# in_out.net
KiCad netlist of a schematic drawn in Altium Designer
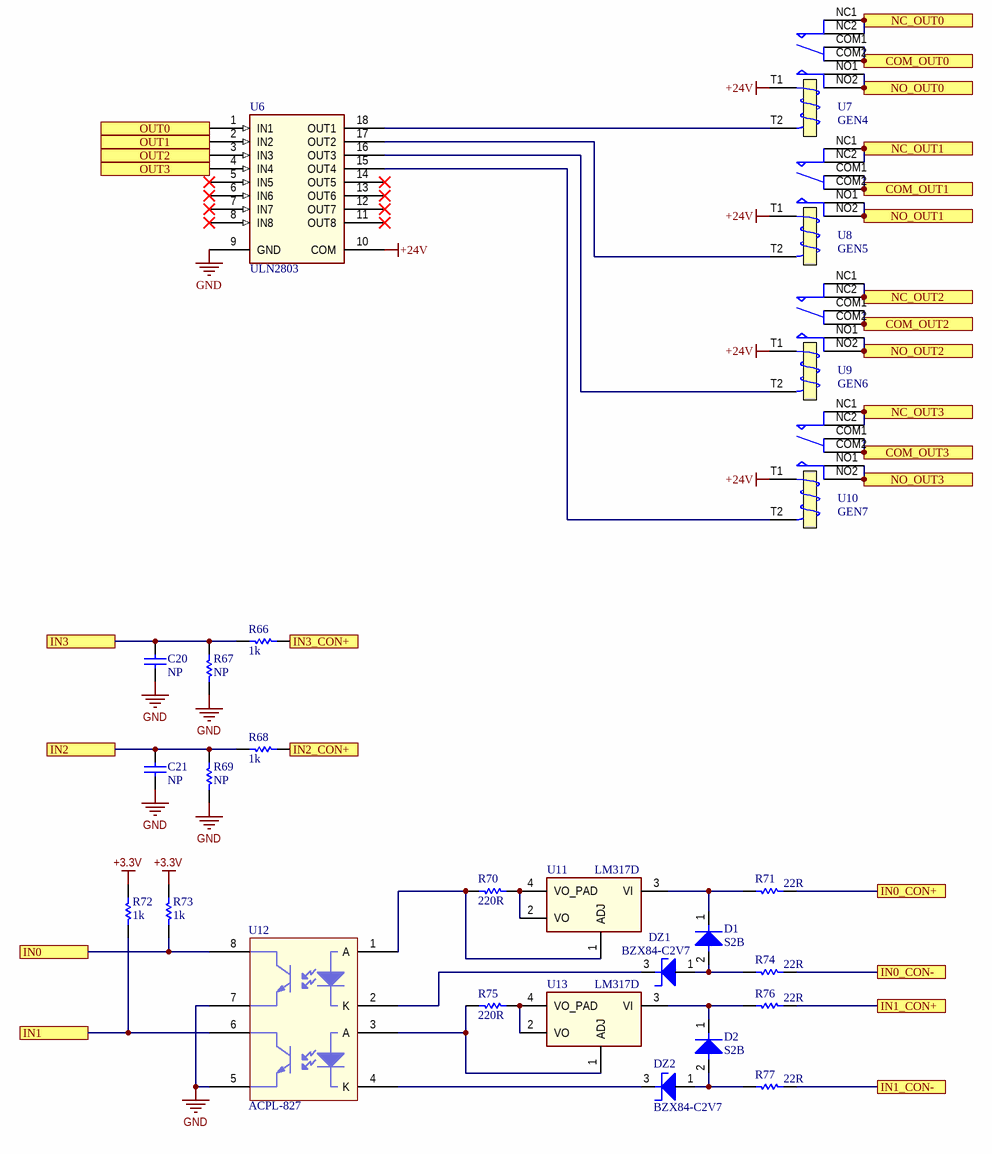
[diagram p0: in_out.SchDoc]

(export (version "E")
  (design (tool "Eeschema 10.0.6"))
  (components
    (comp (ref "C20")
      (value "NP")
      (footprint "0603_[1608]")
      (description "Ceramic X7R 50V")
      (fields (field (name "PUBLISHER") "Altium Limited"))
      (libsource (lib "DEVELER_Library") (part "Cap"))
    )
    (comp (ref "C21")
      (value "NP")
      (footprint "0603_[1608]")
      (description "Ceramic X7R 50V")
      (fields (field (name "PUBLISHER") "Altium Limited"))
      (libsource (lib "DEVELER_Library") (part "Cap"))
    )
    (comp (ref "D1")
      (value "S2B")
      (footprint "DO214AA_K1-A2_SMB")
      (description "S2B Diode")
      (libsource (lib "DEVELER_Library") (part "Diode"))
    )
    (comp (ref "D2")
      (value "S2B")
      (footprint "DO214AA_K1-A2_SMB")
      (description "S2B Diode")
      (libsource (lib "DEVELER_Library") (part "Diode"))
    )
    (comp (ref "DZ1")
      (value "BZX84-C2V7")
      (footprint "SOT-23")
      (description "Zener 2,7V")
      (libsource (lib "DEVELER_Library") (part "ZENER_BZX"))
    )
    (comp (ref "DZ2")
      (value "BZX84-C2V7")
      (footprint "SOT-23")
      (description "Zener 2,7V")
      (libsource (lib "DEVELER_Library") (part "ZENER_BZX"))
    )
    (comp (ref "R66")
      (value "1k")
      (footprint "0603_[1608]")
      (description "Resistor")
      (libsource (lib "DEVELER_Library") (part "Res1"))
    )
    (comp (ref "R67")
      (value "NP")
      (footprint "0603_[1608]")
      (description "Resistor")
      (libsource (lib "DEVELER_Library") (part "Res1"))
    )
    (comp (ref "R68")
      (value "1k")
      (footprint "0603_[1608]")
      (description "Resistor")
      (libsource (lib "DEVELER_Library") (part "Res1"))
    )
    (comp (ref "R69")
      (value "NP")
      (footprint "0603_[1608]")
      (description "Resistor")
      (libsource (lib "DEVELER_Library") (part "Res1"))
    )
    (comp (ref "R70")
      (value "220R")
      (footprint "0603_[1608]")
      (description "Resistor")
      (libsource (lib "DEVELER_Library") (part "Res1"))
    )
    (comp (ref "R71")
      (value "22R")
      (footprint "0603_[1608]")
      (description "Resistor")
      (libsource (lib "DEVELER_Library") (part "Res1"))
    )
    (comp (ref "R72")
      (value "1k")
      (footprint "0603_[1608]")
      (description "Resistor")
      (libsource (lib "DEVELER_Library") (part "Res1"))
    )
    (comp (ref "R73")
      (value "1k")
      (footprint "0603_[1608]")
      (description "Resistor")
      (libsource (lib "DEVELER_Library") (part "Res1"))
    )
    (comp (ref "R74")
      (value "22R")
      (footprint "0603_[1608]")
      (description "Resistor")
      (libsource (lib "DEVELER_Library") (part "Res1"))
    )
    (comp (ref "R75")
      (value "220R")
      (footprint "0603_[1608]")
      (description "Resistor")
      (libsource (lib "DEVELER_Library") (part "Res1"))
    )
    (comp (ref "R76")
      (value "22R")
      (footprint "0603_[1608]")
      (description "Resistor")
      (libsource (lib "DEVELER_Library") (part "Res1"))
    )
    (comp (ref "R77")
      (value "22R")
      (footprint "0603_[1608]")
      (description "Resistor")
      (libsource (lib "DEVELER_Library") (part "Res1"))
    )
    (comp (ref "U6")
      (value "ULN2803")
      (footprint "SOIC18")
      (description "BJT Darlinton Array")
      (libsource (lib "DEVELER_Library") (part "ULN2803"))
    )
    (comp (ref "U7")
      (value "GEN4")
      (footprint "relays_spco_thd_28x12mm_5mm")
      (description "Rele NT75CS16DC12V0.415.0 16A 12V")
      (libsource (lib "develer_library") (part "Relay SPCO_8pin"))
    )
    (comp (ref "U8")
      (value "GEN5")
      (footprint "relays_spco_thd_28x12mm_5mm")
      (description "Rele NT75CS16DC12V0.415.0 16A 12V")
      (libsource (lib "develer_library") (part "Relay SPCO_8pin"))
    )
    (comp (ref "U9")
      (value "GEN6")
      (footprint "relays_spco_thd_28x12mm_5mm")
      (description "Rele NT75CS16DC12V0.415.0 16A 12V")
      (libsource (lib "develer_library") (part "Relay SPCO_8pin"))
    )
    (comp (ref "U10")
      (value "GEN7")
      (footprint "relays_spco_thd_28x12mm_5mm")
      (description "Rele NT75CS16DC12V0.415.0 16A 12V")
      (libsource (lib "develer_library") (part "Relay SPCO_8pin"))
    )
    (comp (ref "U11")
      (value "LM317D")
      (footprint "SOT-223")
      (description "3-Terminal Adjustable Regulator, 3-pin SOT-223")
      (libsource (lib "DEVELER_Library") (part "LM317AT"))
    )
    (comp (ref "U12")
      (value "ACPL-827")
      (footprint "SOIC8_OPTO")
      (description "Optocoupler")
      (libsource (lib "DEVELER_Library") (part "optocoupler 2ch"))
    )
    (comp (ref "U13")
      (value "LM317D")
      (footprint "SOT-223")
      (description "3-Terminal Adjustable Regulator, 3-pin SOT-223")
      (libsource (lib "DEVELER_Library") (part "LM317AT"))
    )
  )
  (nets
    (net (code "1") (name "+3.3V") (class "Default")
      (node (ref "R72") (pin "2") (pinfunction "2_2") (pintype "passive"))
      (node (ref "R73") (pin "2") (pinfunction "2_2") (pintype "passive"))
    )
    (net (code "2") (name "+24V") (class "Default")
      (node (ref "U10") (pin "T1") (pinfunction "T1_T1") (pintype "passive"))
      (node (ref "U6") (pin "10") (pinfunction "COM_10") (pintype "passive"))
      (node (ref "U7") (pin "T1") (pinfunction "T1_T1") (pintype "passive"))
      (node (ref "U8") (pin "T1") (pinfunction "T1_T1") (pintype "passive"))
      (node (ref "U9") (pin "T1") (pinfunction "T1_T1") (pintype "passive"))
    )
    (net (code "3") (name "/COM_OUT0") (class "Default")
      (node (ref "U7") (pin "COM1") (pinfunction "COM1_COM1") (pintype "passive"))
      (node (ref "U7") (pin "COM2") (pinfunction "COM2_COM2") (pintype "passive"))
    )
    (net (code "4") (name "/COM_OUT1") (class "Default")
      (node (ref "U8") (pin "COM1") (pinfunction "COM1_COM1") (pintype "passive"))
      (node (ref "U8") (pin "COM2") (pinfunction "COM2_COM2") (pintype "passive"))
    )
    (net (code "5") (name "/COM_OUT2") (class "Default")
      (node (ref "U9") (pin "COM1") (pinfunction "COM1_COM1") (pintype "passive"))
      (node (ref "U9") (pin "COM2") (pinfunction "COM2_COM2") (pintype "passive"))
    )
    (net (code "6") (name "/COM_OUT3") (class "Default")
      (node (ref "U10") (pin "COM1") (pinfunction "COM1_COM1") (pintype "passive"))
      (node (ref "U10") (pin "COM2") (pinfunction "COM2_COM2") (pintype "passive"))
    )
    (net (code "7") (name "/IN0") (class "Default")
      (node (ref "R73") (pin "1") (pinfunction "1_1") (pintype "passive"))
      (node (ref "U12") (pin "8") (pinfunction "8_8") (pintype "power_in"))
    )
    (net (code "8") (name "/IN0_CON+") (class "Default")
      (node (ref "R71") (pin "2") (pinfunction "2_2") (pintype "passive"))
    )
    (net (code "9") (name "/IN0_CON-") (class "Default")
      (node (ref "R74") (pin "2") (pinfunction "2_2") (pintype "passive"))
    )
    (net (code "10") (name "/IN1") (class "Default")
      (node (ref "R72") (pin "1") (pinfunction "1_1") (pintype "passive"))
      (node (ref "U12") (pin "6") (pinfunction "6_6") (pintype "power_in"))
    )
    (net (code "11") (name "/IN1_CON+") (class "Default")
      (node (ref "R76") (pin "2") (pinfunction "2_2") (pintype "passive"))
    )
    (net (code "12") (name "/IN1_CON-") (class "Default")
      (node (ref "R77") (pin "2") (pinfunction "2_2") (pintype "passive"))
    )
    (net (code "13") (name "/IN2") (class "Default")
      (node (ref "C21") (pin "2") (pinfunction "2_2") (pintype "passive"))
      (node (ref "R68") (pin "2") (pinfunction "2_2") (pintype "passive"))
      (node (ref "R69") (pin "2") (pinfunction "2_2") (pintype "passive"))
    )
    (net (code "14") (name "/IN2_CON+") (class "Default")
      (node (ref "R68") (pin "1") (pinfunction "1_1") (pintype "passive"))
    )
    (net (code "15") (name "/IN3") (class "Default")
      (node (ref "C20") (pin "2") (pinfunction "2_2") (pintype "passive"))
      (node (ref "R66") (pin "2") (pinfunction "2_2") (pintype "passive"))
      (node (ref "R67") (pin "2") (pinfunction "2_2") (pintype "passive"))
    )
    (net (code "16") (name "/IN3_CON+") (class "Default")
      (node (ref "R66") (pin "1") (pinfunction "1_1") (pintype "passive"))
    )
    (net (code "17") (name "/NC_OUT0") (class "Default")
      (node (ref "U7") (pin "NC1") (pinfunction "NC1_NC1") (pintype "passive"))
      (node (ref "U7") (pin "NC2") (pinfunction "NC2_NC2") (pintype "passive"))
    )
    (net (code "18") (name "/NC_OUT1") (class "Default")
      (node (ref "U8") (pin "NC1") (pinfunction "NC1_NC1") (pintype "passive"))
      (node (ref "U8") (pin "NC2") (pinfunction "NC2_NC2") (pintype "passive"))
    )
    (net (code "19") (name "/NC_OUT2") (class "Default")
      (node (ref "U9") (pin "NC1") (pinfunction "NC1_NC1") (pintype "passive"))
      (node (ref "U9") (pin "NC2") (pinfunction "NC2_NC2") (pintype "passive"))
    )
    (net (code "20") (name "/NC_OUT3") (class "Default")
      (node (ref "U10") (pin "NC1") (pinfunction "NC1_NC1") (pintype "passive"))
      (node (ref "U10") (pin "NC2") (pinfunction "NC2_NC2") (pintype "passive"))
    )
    (net (code "21") (name "/NO_OUT0") (class "Default")
      (node (ref "U7") (pin "NO1") (pinfunction "NO1_NO1") (pintype "passive"))
      (node (ref "U7") (pin "NO2") (pinfunction "NO2_NO2") (pintype "passive"))
    )
    (net (code "22") (name "/NO_OUT1") (class "Default")
      (node (ref "U8") (pin "NO1") (pinfunction "NO1_NO1") (pintype "passive"))
      (node (ref "U8") (pin "NO2") (pinfunction "NO2_NO2") (pintype "passive"))
    )
    (net (code "23") (name "/NO_OUT2") (class "Default")
      (node (ref "U9") (pin "NO1") (pinfunction "NO1_NO1") (pintype "passive"))
      (node (ref "U9") (pin "NO2") (pinfunction "NO2_NO2") (pintype "passive"))
    )
    (net (code "24") (name "/NO_OUT3") (class "Default")
      (node (ref "U10") (pin "NO1") (pinfunction "NO1_NO1") (pintype "passive"))
      (node (ref "U10") (pin "NO2") (pinfunction "NO2_NO2") (pintype "passive"))
    )
    (net (code "25") (name "/OUT0") (class "Default")
      (node (ref "U6") (pin "1") (pinfunction "IN1_1") (pintype "input"))
    )
    (net (code "26") (name "/OUT1") (class "Default")
      (node (ref "U6") (pin "2") (pinfunction "IN2_2") (pintype "input"))
    )
    (net (code "27") (name "/OUT2") (class "Default")
      (node (ref "U6") (pin "3") (pinfunction "IN3_3") (pintype "input"))
    )
    (net (code "28") (name "/OUT3") (class "Default")
      (node (ref "U6") (pin "4") (pinfunction "IN4_4") (pintype "input"))
    )
    (net (code "29") (name "GND") (class "Default")
      (node (ref "C20") (pin "1") (pinfunction "1_1") (pintype "passive"))
      (node (ref "C21") (pin "1") (pinfunction "1_1") (pintype "passive"))
      (node (ref "R67") (pin "1") (pinfunction "1_1") (pintype "passive"))
      (node (ref "R69") (pin "1") (pinfunction "1_1") (pintype "passive"))
      (node (ref "U12") (pin "5") (pinfunction "5_5") (pintype "power_in"))
      (node (ref "U12") (pin "7") (pinfunction "7_7") (pintype "power_in"))
      (node (ref "U6") (pin "9") (pinfunction "GND_9") (pintype "power_in"))
    )
    (net (code "30") (name "Net-(D1-A)") (class "Default")
      (node (ref "D1") (pin "2") (pinfunction "A_2") (pintype "passive"))
      (node (ref "DZ1") (pin "1") (pinfunction "A_1") (pintype "passive"))
      (node (ref "R74") (pin "1") (pinfunction "1_1") (pintype "passive"))
    )
    (net (code "31") (name "Net-(D1-K)") (class "Default")
      (node (ref "D1") (pin "1") (pinfunction "K_1") (pintype "passive"))
      (node (ref "R71") (pin "1") (pinfunction "1_1") (pintype "passive"))
      (node (ref "U11") (pin "3") (pinfunction "VI_3") (pintype "passive"))
    )
    (net (code "32") (name "Net-(D2-A)") (class "Default")
      (node (ref "D2") (pin "2") (pinfunction "A_2") (pintype "passive"))
      (node (ref "DZ2") (pin "1") (pinfunction "A_1") (pintype "passive"))
      (node (ref "R77") (pin "1") (pinfunction "1_1") (pintype "passive"))
    )
    (net (code "33") (name "Net-(D2-K)") (class "Default")
      (node (ref "D2") (pin "1") (pinfunction "K_1") (pintype "passive"))
      (node (ref "R76") (pin "1") (pinfunction "1_1") (pintype "passive"))
      (node (ref "U13") (pin "3") (pinfunction "VI_3") (pintype "passive"))
    )
    (net (code "34") (name "Net-(DZ1-K)") (class "Default")
      (node (ref "DZ1") (pin "3") (pinfunction "K_3") (pintype "passive"))
      (node (ref "U12") (pin "2") (pinfunction "K_2") (pintype "power_in"))
    )
    (net (code "35") (name "Net-(DZ2-K)") (class "Default")
      (node (ref "DZ2") (pin "3") (pinfunction "K_3") (pintype "passive"))
      (node (ref "U12") (pin "4") (pinfunction "K_4") (pintype "power_in"))
    )
    (net (code "36") (name "Net-(U6-OUT1)") (class "Default")
      (node (ref "U6") (pin "18") (pinfunction "OUT1_18") (pintype "open_collector"))
      (node (ref "U7") (pin "T2") (pinfunction "T2_T2") (pintype "passive"))
    )
    (net (code "37") (name "Net-(U6-OUT2)") (class "Default")
      (node (ref "U6") (pin "17") (pinfunction "OUT2_17") (pintype "open_collector"))
      (node (ref "U8") (pin "T2") (pinfunction "T2_T2") (pintype "passive"))
    )
    (net (code "38") (name "Net-(U6-OUT3)") (class "Default")
      (node (ref "U6") (pin "16") (pinfunction "OUT3_16") (pintype "open_collector"))
      (node (ref "U9") (pin "T2") (pinfunction "T2_T2") (pintype "passive"))
    )
    (net (code "39") (name "Net-(U6-OUT4)") (class "Default")
      (node (ref "U10") (pin "T2") (pinfunction "T2_T2") (pintype "passive"))
      (node (ref "U6") (pin "15") (pinfunction "OUT4_15") (pintype "open_collector"))
    )
    (net (code "40") (name "Net-(U11-ADJ)") (class "Default")
      (node (ref "R70") (pin "1") (pinfunction "1_1") (pintype "passive"))
      (node (ref "U11") (pin "1") (pinfunction "ADJ_1") (pintype "passive"))
      (node (ref "U12") (pin "1") (pinfunction "A_1") (pintype "power_in"))
    )
    (net (code "41") (name "Net-(U11-VO)") (class "Default")
      (node (ref "R70") (pin "2") (pinfunction "2_2") (pintype "passive"))
      (node (ref "U11") (pin "2") (pinfunction "VO_2") (pintype "passive"))
      (node (ref "U11") (pin "4") (pinfunction "VO_PAD_4") (pintype "passive"))
    )
    (net (code "42") (name "Net-(U13-ADJ)") (class "Default")
      (node (ref "R75") (pin "1") (pinfunction "1_1") (pintype "passive"))
      (node (ref "U12") (pin "3") (pinfunction "A_3") (pintype "power_in"))
      (node (ref "U13") (pin "1") (pinfunction "ADJ_1") (pintype "passive"))
    )
    (net (code "43") (name "Net-(U13-VO)") (class "Default")
      (node (ref "R75") (pin "2") (pinfunction "2_2") (pintype "passive"))
      (node (ref "U13") (pin "2") (pinfunction "VO_2") (pintype "passive"))
      (node (ref "U13") (pin "4") (pinfunction "VO_PAD_4") (pintype "passive"))
    )
    (net (code "44") (name "unconnected-(U6-IN5-Pad5)") (class "Default")
      (node (ref "U6") (pin "5") (pinfunction "IN5_5") (pintype "input+no_connect"))
    )
    (net (code "45") (name "unconnected-(U6-IN6-Pad6)") (class "Default")
      (node (ref "U6") (pin "6") (pinfunction "IN6_6") (pintype "input+no_connect"))
    )
    (net (code "46") (name "unconnected-(U6-IN7-Pad7)") (class "Default")
      (node (ref "U6") (pin "7") (pinfunction "IN7_7") (pintype "input+no_connect"))
    )
    (net (code "47") (name "unconnected-(U6-IN8-Pad8)") (class "Default")
      (node (ref "U6") (pin "8") (pinfunction "IN8_8") (pintype "input+no_connect"))
    )
    (net (code "48") (name "unconnected-(U6-OUT5-Pad14)") (class "Default")
      (node (ref "U6") (pin "14") (pinfunction "OUT5_14") (pintype "open_collector+no_connect"))
    )
    (net (code "49") (name "unconnected-(U6-OUT6-Pad13)") (class "Default")
      (node (ref "U6") (pin "13") (pinfunction "OUT6_13") (pintype "open_collector+no_connect"))
    )
    (net (code "50") (name "unconnected-(U6-OUT7-Pad12)") (class "Default")
      (node (ref "U6") (pin "12") (pinfunction "OUT7_12") (pintype "open_collector+no_connect"))
    )
    (net (code "51") (name "unconnected-(U6-OUT8-Pad11)") (class "Default")
      (node (ref "U6") (pin "11") (pinfunction "OUT8_11") (pintype "open_collector+no_connect"))
    )
  )
)
